# AUDIO_AMP_NB2A.net
KiCad netlist of a schematic drawn in Altium Designer
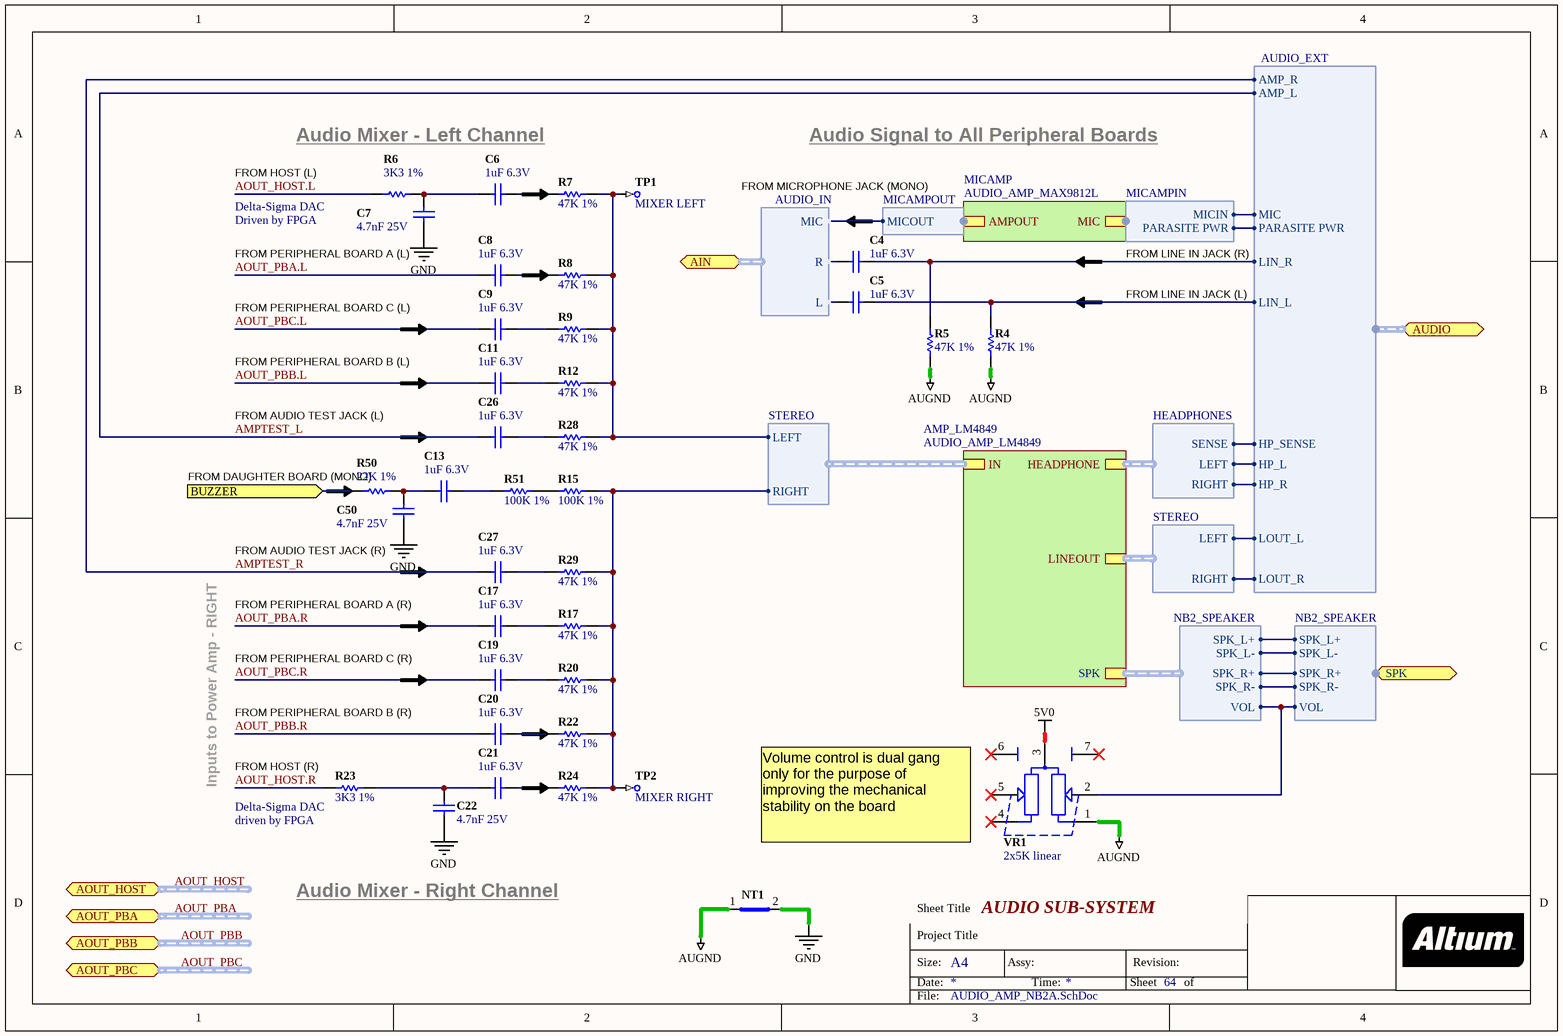
[diagram p0: AUDIO_AMP_NB2A.SchDoc]

(export (version "E")
  (design (tool "Eeschema 10.0.6"))
  (components
    (comp (ref "C4")
      (value "1uF 6.3V")
      (footprint "CAPC1005-STAR")
      (description "Capacitor, Ceramic, 1uF 10% 6.3V 0402 (1005) X5R")
      (fields (field (name "TOLERANCE") "10 %"))
      (libsource (lib "altium-import") (part "root_3_CAP-NP_"))
    )
    (comp (ref "C5")
      (value "1uF 6.3V")
      (footprint "CAPC1005-STAR")
      (description "Capacitor, Ceramic, 1uF 10% 6.3V 0402 (1005) X5R")
      (fields (field (name "TOLERANCE") "10 %"))
      (libsource (lib "altium-import") (part "root_3_CAP-NP_"))
    )
    (comp (ref "C6")
      (value "1uF 6.3V")
      (footprint "CAPC1005-STAR")
      (description "Capacitor, Ceramic, 1uF 10% 6.3V 0402 (1005) X5R")
      (fields (field (name "TOLERANCE") "10 %"))
      (libsource (lib "altium-import") (part "root_3_CAP-NP_"))
    )
    (comp (ref "C7")
      (value "4.7nF 25V")
      (footprint "CAPC1005-STAR")
      (description "Capacitor, Ceramic, 4.7nF 10% 25V 0402 (1005) X7R")
      (fields (field (name "TOLERANCE") "10 %"))
      (libsource (lib "altium-import") (part "root_0_CAP-NP_"))
    )
    (comp (ref "C8")
      (value "1uF 6.3V")
      (footprint "CAPC1005-STAR")
      (description "Capacitor, Ceramic, 1uF 10% 6.3V 0402 (1005) X5R")
      (fields (field (name "TOLERANCE") "10 %"))
      (libsource (lib "altium-import") (part "root_3_CAP-NP_"))
    )
    (comp (ref "C9")
      (value "1uF 6.3V")
      (footprint "CAPC1005-STAR")
      (description "Capacitor, Ceramic, 1uF 10% 6.3V 0402 (1005) X5R")
      (fields (field (name "TOLERANCE") "10 %"))
      (libsource (lib "altium-import") (part "root_3_CAP-NP_"))
    )
    (comp (ref "C11")
      (value "1uF 6.3V")
      (footprint "CAPC1005-STAR")
      (description "Capacitor, Ceramic, 1uF 10% 6.3V 0402 (1005) X5R")
      (fields (field (name "TOLERANCE") "10 %"))
      (libsource (lib "altium-import") (part "root_3_CAP-NP_"))
    )
    (comp (ref "C13")
      (value "1uF 6.3V")
      (footprint "CAPC1005-STAR")
      (description "Capacitor, Ceramic, 1uF 10% 6.3V 0402 (1005) X5R")
      (fields (field (name "TOLERANCE") "10 %"))
      (libsource (lib "altium-import") (part "root_3_CAP-NP_"))
    )
    (comp (ref "C17")
      (value "1uF 6.3V")
      (footprint "CAPC1005-STAR")
      (description "Capacitor, Ceramic, 1uF 10% 6.3V 0402 (1005) X5R")
      (fields (field (name "TOLERANCE") "10 %"))
      (libsource (lib "altium-import") (part "root_3_CAP-NP_"))
    )
    (comp (ref "C19")
      (value "1uF 6.3V")
      (footprint "CAPC1005-STAR")
      (description "Capacitor, Ceramic, 1uF 10% 6.3V 0402 (1005) X5R")
      (fields (field (name "TOLERANCE") "10 %"))
      (libsource (lib "altium-import") (part "root_3_CAP-NP_"))
    )
    (comp (ref "C20")
      (value "1uF 6.3V")
      (footprint "CAPC1005-STAR")
      (description "Capacitor, Ceramic, 1uF 10% 6.3V 0402 (1005) X5R")
      (fields (field (name "TOLERANCE") "10 %"))
      (libsource (lib "altium-import") (part "root_3_CAP-NP_"))
    )
    (comp (ref "C21")
      (value "1uF 6.3V")
      (footprint "CAPC1005-STAR")
      (description "Capacitor, Ceramic, 1uF 10% 6.3V 0402 (1005) X5R")
      (fields (field (name "TOLERANCE") "10 %"))
      (libsource (lib "altium-import") (part "root_3_CAP-NP_"))
    )
    (comp (ref "C22")
      (value "4.7nF 25V")
      (footprint "CAPC1005-STAR")
      (description "Capacitor, Ceramic, 4.7nF 10% 25V 0402 (1005) X7R")
      (fields (field (name "TOLERANCE") "10 %"))
      (libsource (lib "altium-import") (part "root_0_CAP-NP_"))
    )
    (comp (ref "C26")
      (value "1uF 6.3V")
      (footprint "CAPC1005-STAR")
      (description "Capacitor, Ceramic, 1uF 10% 6.3V 0402 (1005) X5R")
      (fields (field (name "TOLERANCE") "10 %"))
      (libsource (lib "altium-import") (part "root_3_CAP-NP_"))
    )
    (comp (ref "C27")
      (value "1uF 6.3V")
      (footprint "CAPC1005-STAR")
      (description "Capacitor, Ceramic, 1uF 10% 6.3V 0402 (1005) X5R")
      (fields (field (name "TOLERANCE") "10 %"))
      (libsource (lib "altium-import") (part "root_3_CAP-NP_"))
    )
    (comp (ref "C50")
      (value "4.7nF 25V")
      (footprint "CAPC1005-STAR")
      (description "Capacitor, Ceramic, 4.7nF 10% 25V 0402 (1005) X7R")
      (fields (field (name "TOLERANCE") "10 %"))
      (libsource (lib "altium-import") (part "root_0_CAP-NP_"))
    )
    (comp (ref "NT1")
      (value "Net Tie SMT2")
      (footprint "NETTIE-SMT2-31X39")
      (description "Net-Tie, Surface Mount, 2 x 2.0mm x 0.8mm SMT Pads - For 0.8mm Track")
      (libsource (lib "AltiumDesignLibrary") (part "NETTIE-SMT2"))
    )
    (comp (ref "R4")
      (value "47K 1%")
      (footprint "RESC1005-STAR")
      (description "Resistor, 47K 1% 0402 (1005)")
      (fields (field (name "TOLERANCE") "1 %"))
      (libsource (lib "altium-import") (part "root_2_RES_"))
    )
    (comp (ref "R5")
      (value "47K 1%")
      (footprint "RESC1005-STAR")
      (description "Resistor, 47K 1% 0402 (1005)")
      (fields (field (name "TOLERANCE") "1 %"))
      (libsource (lib "altium-import") (part "root_2_RES_"))
    )
    (comp (ref "R6")
      (value "3K3 1%")
      (footprint "RESC1005-STAR")
      (description "Resistor, 3K3 1% 0402 (1005)")
      (fields (field (name "TOLERANCE") "1 %"))
      (libsource (lib "altium-import") (part "root_1_RES_"))
    )
    (comp (ref "R7")
      (value "47K 1%")
      (footprint "RESC1005-STAR")
      (description "Resistor, 47K 1% 0402 (1005)")
      (fields (field (name "TOLERANCE") "1 %"))
      (libsource (lib "altium-import") (part "root_1_RES_"))
    )
    (comp (ref "R8")
      (value "47K 1%")
      (footprint "RESC1005-STAR")
      (description "Resistor, 47K 1% 0402 (1005)")
      (fields (field (name "TOLERANCE") "1 %"))
      (libsource (lib "altium-import") (part "root_1_RES_"))
    )
    (comp (ref "R9")
      (value "47K 1%")
      (footprint "RESC1005-STAR")
      (description "Resistor, 47K 1% 0402 (1005)")
      (fields (field (name "TOLERANCE") "1 %"))
      (libsource (lib "altium-import") (part "root_1_RES_"))
    )
    (comp (ref "R12")
      (value "47K 1%")
      (footprint "RESC1005-STAR")
      (description "Resistor, 47K 1% 0402 (1005)")
      (fields (field (name "TOLERANCE") "1 %"))
      (libsource (lib "altium-import") (part "root_1_RES_"))
    )
    (comp (ref "R15")
      (value "100K 1%")
      (footprint "RESC1005-STAR")
      (description "Resistor, 100K 1% 0402 (1005)")
      (fields (field (name "TOLERANCE") "1 %"))
      (libsource (lib "altium-import") (part "root_1_RES_"))
    )
    (comp (ref "R17")
      (value "47K 1%")
      (footprint "RESC1005-STAR")
      (description "Resistor, 47K 1% 0402 (1005)")
      (fields (field (name "TOLERANCE") "1 %"))
      (libsource (lib "altium-import") (part "root_1_RES_"))
    )
    (comp (ref "R20")
      (value "47K 1%")
      (footprint "RESC1005-STAR")
      (description "Resistor, 47K 1% 0402 (1005)")
      (fields (field (name "TOLERANCE") "1 %"))
      (libsource (lib "altium-import") (part "root_1_RES_"))
    )
    (comp (ref "R22")
      (value "47K 1%")
      (footprint "RESC1005-STAR")
      (description "Resistor, 47K 1% 0402 (1005)")
      (fields (field (name "TOLERANCE") "1 %"))
      (libsource (lib "altium-import") (part "root_1_RES_"))
    )
    (comp (ref "R23")
      (value "3K3 1%")
      (footprint "RESC1005-STAR")
      (description "Resistor, 3K3 1% 0402 (1005)")
      (fields (field (name "TOLERANCE") "1 %"))
      (libsource (lib "altium-import") (part "root_1_RES_"))
    )
    (comp (ref "R24")
      (value "47K 1%")
      (footprint "RESC1005-STAR")
      (description "Resistor, 47K 1% 0402 (1005)")
      (fields (field (name "TOLERANCE") "1 %"))
      (libsource (lib "altium-import") (part "root_1_RES_"))
    )
    (comp (ref "R28")
      (value "47K 1%")
      (footprint "RESC1005-STAR")
      (description "Resistor, 47K 1% 0402 (1005)")
      (fields (field (name "TOLERANCE") "1 %"))
      (libsource (lib "altium-import") (part "root_1_RES_"))
    )
    (comp (ref "R29")
      (value "47K 1%")
      (footprint "RESC1005-STAR")
      (description "Resistor, 47K 1% 0402 (1005)")
      (fields (field (name "TOLERANCE") "1 %"))
      (libsource (lib "altium-import") (part "root_1_RES_"))
    )
    (comp (ref "R50")
      (value "22K 1%")
      (footprint "RESC1005-STAR")
      (description "Resistor, 22K 1% 0402 (1005)")
      (fields (field (name "TOLERANCE") "1 %"))
      (libsource (lib "altium-import") (part "root_1_RES_"))
    )
    (comp (ref "R51")
      (value "100K 1%")
      (footprint "RESC1005-STAR")
      (description "Resistor, 100K 1% 0402 (1005)")
      (fields (field (name "TOLERANCE") "1 %"))
      (libsource (lib "altium-import") (part "root_1_RES_"))
    )
    (comp (ref "TP1")
      (value "MIXER LEFT")
      (footprint "TestPin")
      (description "Test Point, PCB Mount with Silkscreen Box")
      (libsource (lib "AltiumDesignLibrary") (part "TestPin"))
    )
    (comp (ref "TP2")
      (value "MIXER RIGHT")
      (footprint "TestPin")
      (description "Test Point, PCB Mount with Silkscreen Box")
      (libsource (lib "AltiumDesignLibrary") (part "TestPin"))
    )
    (comp (ref "VR1")
      (value "2x5K linear")
      (footprint "POT-R0911G-A1")
      (description "Potentiometer, 2 x 5K Linear 9mm PCB Mount Fluted Shaft")
      (libsource (lib "altium-import") (part "root_2_POT-DUAL_GANG_"))
    )
  )
  (nets
    (net (code "11") (name "/AMPTEST_L") (class "Default")
      (node (ref "C26") (pin "2") (pinfunction "2_2") (pintype "passive"))
    )
    (net (code "12") (name "/AMPTEST_R") (class "Default")
      (node (ref "C27") (pin "2") (pinfunction "2_2") (pintype "passive"))
    )
    (net (code "13") (name "/AOUT_HOST.L") (class "Default")
      (node (ref "R6") (pin "1") (pinfunction "1_1") (pintype "passive"))
    )
    (net (code "14") (name "/AOUT_HOST.R") (class "Default")
      (node (ref "R23") (pin "1") (pinfunction "1_1") (pintype "passive"))
    )
    (net (code "15") (name "/AOUT_PBA.L") (class "Default")
      (node (ref "C8") (pin "2") (pinfunction "2_2") (pintype "passive"))
    )
    (net (code "16") (name "/AOUT_PBA.R") (class "Default")
      (node (ref "C17") (pin "2") (pinfunction "2_2") (pintype "passive"))
    )
    (net (code "17") (name "/AOUT_PBB.L") (class "Default")
      (node (ref "C11") (pin "2") (pinfunction "2_2") (pintype "passive"))
    )
    (net (code "18") (name "/AOUT_PBB.R") (class "Default")
      (node (ref "C20") (pin "2") (pinfunction "2_2") (pintype "passive"))
    )
    (net (code "19") (name "/AOUT_PBC.L") (class "Default")
      (node (ref "C9") (pin "2") (pinfunction "2_2") (pintype "passive"))
    )
    (net (code "20") (name "/AOUT_PBC.R") (class "Default")
      (node (ref "C19") (pin "2") (pinfunction "2_2") (pintype "passive"))
    )
    (net (code "21") (name "/BUZZER") (class "Default")
      (node (ref "R50") (pin "1") (pinfunction "1_1") (pintype "passive"))
    )
    (net (code "25") (name "/L") (class "Default")
      (node (ref "C5") (pin "2") (pinfunction "2_2") (pintype "passive"))
    )
    (net (code "26") (name "/LIN_L") (class "Default")
      (node (ref "C5") (pin "1") (pinfunction "1_1") (pintype "passive"))
      (node (ref "R4") (pin "2") (pinfunction "2_2") (pintype "passive"))
    )
    (net (code "27") (name "/LIN_R") (class "Default")
      (node (ref "C4") (pin "1") (pinfunction "1_1") (pintype "passive"))
      (node (ref "R5") (pin "2") (pinfunction "2_2") (pintype "passive"))
    )
    (net (code "34") (name "/R") (class "Default")
      (node (ref "C4") (pin "2") (pinfunction "2_2") (pintype "passive"))
    )
    (net (code "39") (name "/VOL") (class "Default")
      (node (ref "VR1") (pin "2") (pinfunction "2_2") (pintype "passive"))
    )
    (net (code "49") (name "5V0") (class "Default")
      (node (ref "VR1") (pin "3") (pinfunction "3_3") (pintype "passive"))
    )
    (net (code "50") (name "AUGND") (class "Default")
      (node (ref "NT1") (pin "1") (pinfunction "Net1_1") (pintype "passive"))
      (node (ref "R4") (pin "1") (pinfunction "1_1") (pintype "passive"))
      (node (ref "R5") (pin "1") (pinfunction "1_1") (pintype "passive"))
      (node (ref "VR1") (pin "1") (pinfunction "1_1") (pintype "passive"))
    )
    (net (code "51") (name "GND") (class "Default")
      (node (ref "C22") (pin "2") (pinfunction "2_2") (pintype "passive"))
      (node (ref "C50") (pin "2") (pinfunction "2_2") (pintype "passive"))
      (node (ref "C7") (pin "2") (pinfunction "2_2") (pintype "passive"))
      (node (ref "NT1") (pin "2") (pinfunction "Net2_2") (pintype "passive"))
    )
    (net (code "52") (name "Net-(C6-Pad1)") (class "Default")
      (node (ref "C6") (pin "1") (pinfunction "1_1") (pintype "passive"))
      (node (ref "R7") (pin "1") (pinfunction "1_1") (pintype "passive"))
    )
    (net (code "53") (name "Net-(C6-Pad2)") (class "Default")
      (node (ref "C6") (pin "2") (pinfunction "2_2") (pintype "passive"))
      (node (ref "C7") (pin "1") (pinfunction "1_1") (pintype "passive"))
      (node (ref "R6") (pin "2") (pinfunction "2_2") (pintype "passive"))
    )
    (net (code "54") (name "Net-(C8-Pad1)") (class "Default")
      (node (ref "C8") (pin "1") (pinfunction "1_1") (pintype "passive"))
      (node (ref "R8") (pin "1") (pinfunction "1_1") (pintype "passive"))
    )
    (net (code "55") (name "Net-(C9-Pad1)") (class "Default")
      (node (ref "C9") (pin "1") (pinfunction "1_1") (pintype "passive"))
      (node (ref "R9") (pin "1") (pinfunction "1_1") (pintype "passive"))
    )
    (net (code "56") (name "Net-(C11-Pad1)") (class "Default")
      (node (ref "C11") (pin "1") (pinfunction "1_1") (pintype "passive"))
      (node (ref "R12") (pin "1") (pinfunction "1_1") (pintype "passive"))
    )
    (net (code "57") (name "Net-(C13-Pad1)") (class "Default")
      (node (ref "C13") (pin "1") (pinfunction "1_1") (pintype "passive"))
      (node (ref "R51") (pin "1") (pinfunction "1_1") (pintype "passive"))
    )
    (net (code "58") (name "Net-(C13-Pad2)") (class "Default")
      (node (ref "C13") (pin "2") (pinfunction "2_2") (pintype "passive"))
      (node (ref "C50") (pin "1") (pinfunction "1_1") (pintype "passive"))
      (node (ref "R50") (pin "2") (pinfunction "2_2") (pintype "passive"))
    )
    (net (code "59") (name "Net-(C17-Pad1)") (class "Default")
      (node (ref "C17") (pin "1") (pinfunction "1_1") (pintype "passive"))
      (node (ref "R17") (pin "1") (pinfunction "1_1") (pintype "passive"))
    )
    (net (code "60") (name "Net-(C19-Pad1)") (class "Default")
      (node (ref "C19") (pin "1") (pinfunction "1_1") (pintype "passive"))
      (node (ref "R20") (pin "1") (pinfunction "1_1") (pintype "passive"))
    )
    (net (code "61") (name "Net-(C20-Pad1)") (class "Default")
      (node (ref "C20") (pin "1") (pinfunction "1_1") (pintype "passive"))
      (node (ref "R22") (pin "1") (pinfunction "1_1") (pintype "passive"))
    )
    (net (code "62") (name "Net-(C21-Pad1)") (class "Default")
      (node (ref "C21") (pin "1") (pinfunction "1_1") (pintype "passive"))
      (node (ref "R24") (pin "1") (pinfunction "1_1") (pintype "passive"))
    )
    (net (code "63") (name "Net-(C21-Pad2)") (class "Default")
      (node (ref "C21") (pin "2") (pinfunction "2_2") (pintype "passive"))
      (node (ref "C22") (pin "1") (pinfunction "1_1") (pintype "passive"))
      (node (ref "R23") (pin "2") (pinfunction "2_2") (pintype "passive"))
    )
    (net (code "64") (name "Net-(C26-Pad1)") (class "Default")
      (node (ref "C26") (pin "1") (pinfunction "1_1") (pintype "passive"))
      (node (ref "R28") (pin "1") (pinfunction "1_1") (pintype "passive"))
    )
    (net (code "65") (name "Net-(C27-Pad1)") (class "Default")
      (node (ref "C27") (pin "1") (pinfunction "1_1") (pintype "passive"))
      (node (ref "R29") (pin "1") (pinfunction "1_1") (pintype "passive"))
    )
    (net (code "66") (name "Net-(R12-Pad2)") (class "Default")
      (node (ref "R12") (pin "2") (pinfunction "2_2") (pintype "passive"))
      (node (ref "R28") (pin "2") (pinfunction "2_2") (pintype "passive"))
      (node (ref "R7") (pin "2") (pinfunction "2_2") (pintype "passive"))
      (node (ref "R8") (pin "2") (pinfunction "2_2") (pintype "passive"))
      (node (ref "R9") (pin "2") (pinfunction "2_2") (pintype "passive"))
      (node (ref "TP1") (pin "1") (pinfunction "1_1") (pintype "input"))
    )
    (net (code "67") (name "Net-(R15-Pad1)") (class "Default")
      (node (ref "R15") (pin "1") (pinfunction "1_1") (pintype "passive"))
      (node (ref "R51") (pin "2") (pinfunction "2_2") (pintype "passive"))
    )
    (net (code "68") (name "Net-(R15-Pad2)") (class "Default")
      (node (ref "R15") (pin "2") (pinfunction "2_2") (pintype "passive"))
      (node (ref "R17") (pin "2") (pinfunction "2_2") (pintype "passive"))
      (node (ref "R20") (pin "2") (pinfunction "2_2") (pintype "passive"))
      (node (ref "R22") (pin "2") (pinfunction "2_2") (pintype "passive"))
      (node (ref "R24") (pin "2") (pinfunction "2_2") (pintype "passive"))
      (node (ref "R29") (pin "2") (pinfunction "2_2") (pintype "passive"))
      (node (ref "TP2") (pin "1") (pinfunction "1_1") (pintype "input"))
    )
    (net (code "69") (name "unconnected-(VR1-Pad4)") (class "Default")
      (node (ref "VR1") (pin "4") (pinfunction "4_4") (pintype "passive+no_connect"))
    )
    (net (code "70") (name "unconnected-(VR1-Pad5)") (class "Default")
      (node (ref "VR1") (pin "5") (pinfunction "5_5") (pintype "passive+no_connect"))
    )
    (net (code "71") (name "unconnected-(VR1-Pad6)") (class "Default")
      (node (ref "VR1") (pin "6") (pinfunction "6_6") (pintype "passive+no_connect"))
    )
    (net (code "72") (name "unconnected-(VR1-Pad7)") (class "Default")
      (node (ref "VR1") (pin "7") (pinfunction "7_7") (pintype "passive+no_connect"))
    )
  )
)
